# Current_Sensor_v1_0.net
KiCad netlist of a schematic drawn in EAGLE
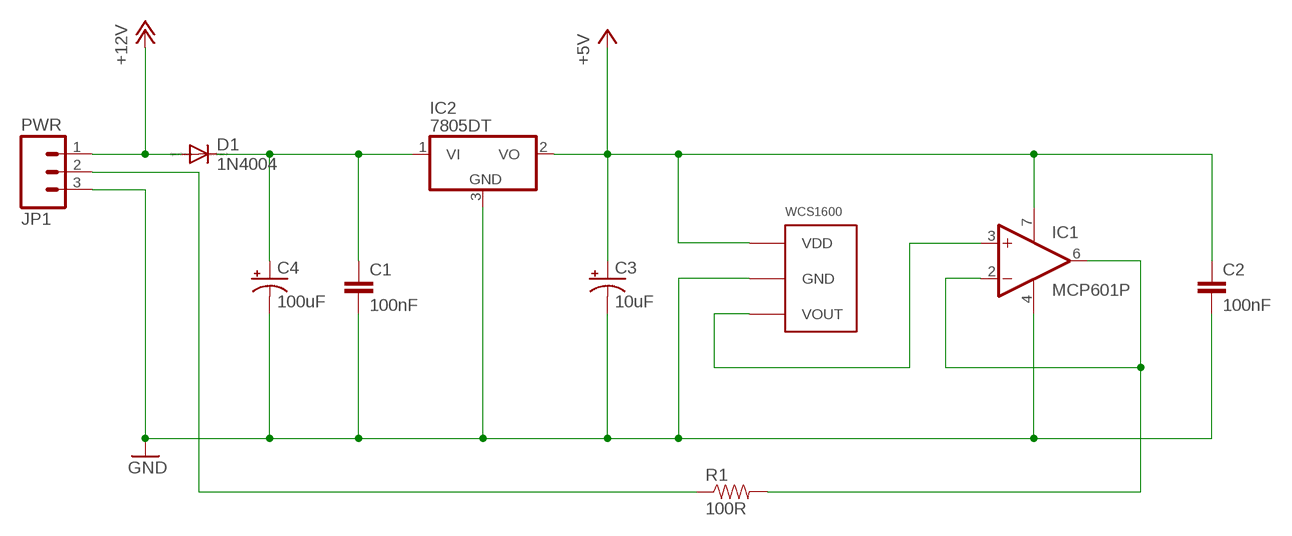
[diagram p0: schematic, sheet 1]

(export (version "E")
  (design (tool "Eeschema 10.0.6"))
  (components
    (comp (ref "C1")
      (value "100nF")
      (footprint "eagle-import:CAP-PTH-SMALL-KIT")
      (libsource (lib "eagle-import") (part "0.1UF-50V-20%(PTH)KIT-EZ"))
    )
    (comp (ref "C2")
      (value "100nF")
      (footprint "eagle-import:CAP-PTH-SMALL-KIT")
      (libsource (lib "eagle-import") (part "0.1UF-50V-20%(PTH)KIT-EZ"))
    )
    (comp (ref "C3")
      (value "10uF")
      (footprint "eagle-import:CPOL-RADIAL-10UF-25V-KIT")
      (libsource (lib "eagle-import") (part "10UF-25V-20%(PTH)KIT"))
    )
    (comp (ref "C4")
      (value "100uF")
      (footprint "eagle-import:CPOL-RADIAL-100UF-25V")
      (libsource (lib "eagle-import") (part "100UF-25V-20%(PTH)"))
    )
    (comp (ref "D1")
      (value "1N4004")
      (footprint "eagle-import:DO41-10")
      (libsource (lib "eagle-import") (part "1N4004"))
    )
    (comp (ref "IC1")
      (value "MCP601P")
      (footprint "eagle-import:DIL08")
      (libsource (lib "eagle-import") (part "MCP601P"))
    )
    (comp (ref "IC2")
      (value "7805DT")
      (footprint "eagle-import:TO252")
      (libsource (lib "eagle-import") (part "78DT05"))
    )
    (comp (ref "JP1")
      (value "PWR")
      (footprint "eagle-import:MOLEX-1X3")
      (libsource (lib "eagle-import") (part "M03POLAR"))
    )
    (comp (ref "R1")
      (value "100R")
      (footprint "eagle-import:AXIAL-0.3")
      (libsource (lib "eagle-import") (part "RESISTORAXIAL-0.3"))
    )
    (comp (ref "U$1")
      (value "WCSXXXX")
      (footprint "eagle-import:WCSXXXX")
      (libsource (lib "eagle-import") (part "WCSXXXX"))
    )
  )
  (nets
    (net (code "1") (name "+5V") (class "Default")
      (node (ref "C2") (pin "1") (pinfunction "1_1") (pintype "passive"))
      (node (ref "C3") (pin "1") (pinfunction "+_1") (pintype "passive"))
      (node (ref "IC1") (pin "7") (pinfunction "V+_7") (pintype "power_in"))
      (node (ref "IC2") (pin "2") (pinfunction "VO_2") (pintype "passive"))
      (node (ref "U$1") (pin "P$1") (pinfunction "VDD_P$1") (pintype "power_in"))
    )
    (net (code "2") (name "+12V") (class "Default")
      (node (ref "D1") (pin "A") (pinfunction "A_A") (pintype "passive"))
      (node (ref "JP1") (pin "1") (pinfunction "1_1") (pintype "passive"))
    )
    (net (code "3") (name "GND") (class "Default")
      (node (ref "C1") (pin "2") (pinfunction "2_2") (pintype "passive"))
      (node (ref "C2") (pin "2") (pinfunction "2_2") (pintype "passive"))
      (node (ref "C3") (pin "2") (pinfunction "-_2") (pintype "passive"))
      (node (ref "C4") (pin "2") (pinfunction "-_2") (pintype "passive"))
      (node (ref "IC1") (pin "4") (pinfunction "V-_4") (pintype "power_in"))
      (node (ref "IC2") (pin "3") (pinfunction "GND_3") (pintype "passive"))
      (node (ref "JP1") (pin "3") (pinfunction "3_3") (pintype "passive"))
      (node (ref "U$1") (pin "P$2") (pinfunction "GND_P$2") (pintype "power_in"))
    )
    (net (code "4") (name "Net-(C4-+)") (class "Default")
      (node (ref "C1") (pin "1") (pinfunction "1_1") (pintype "passive"))
      (node (ref "C4") (pin "1") (pinfunction "+_1") (pintype "passive"))
      (node (ref "D1") (pin "C") (pinfunction "C_C") (pintype "passive"))
      (node (ref "IC2") (pin "1") (pinfunction "VI_1") (pintype "input"))
    )
    (net (code "5") (name "Net-(IC1-+IN)") (class "Default")
      (node (ref "IC1") (pin "3") (pinfunction "+IN_3") (pintype "input"))
      (node (ref "U$1") (pin "P$3") (pinfunction "VOUT_P$3") (pintype "output"))
    )
    (net (code "6") (name "Net-(IC1--IN)") (class "Default")
      (node (ref "IC1") (pin "2") (pinfunction "-IN_2") (pintype "input"))
      (node (ref "IC1") (pin "6") (pinfunction "OUT_6") (pintype "output"))
      (node (ref "R1") (pin "P$2") (pinfunction "2_P$2") (pintype "passive"))
    )
    (net (code "7") (name "Net-(R1-1)") (class "Default")
      (node (ref "JP1") (pin "2") (pinfunction "2_2") (pintype "passive"))
      (node (ref "R1") (pin "P$1") (pinfunction "1_P$1") (pintype "passive"))
    )
  )
)
